# Relay_schematic.net
KiCad netlist of a schematic drawn in Altium Designer
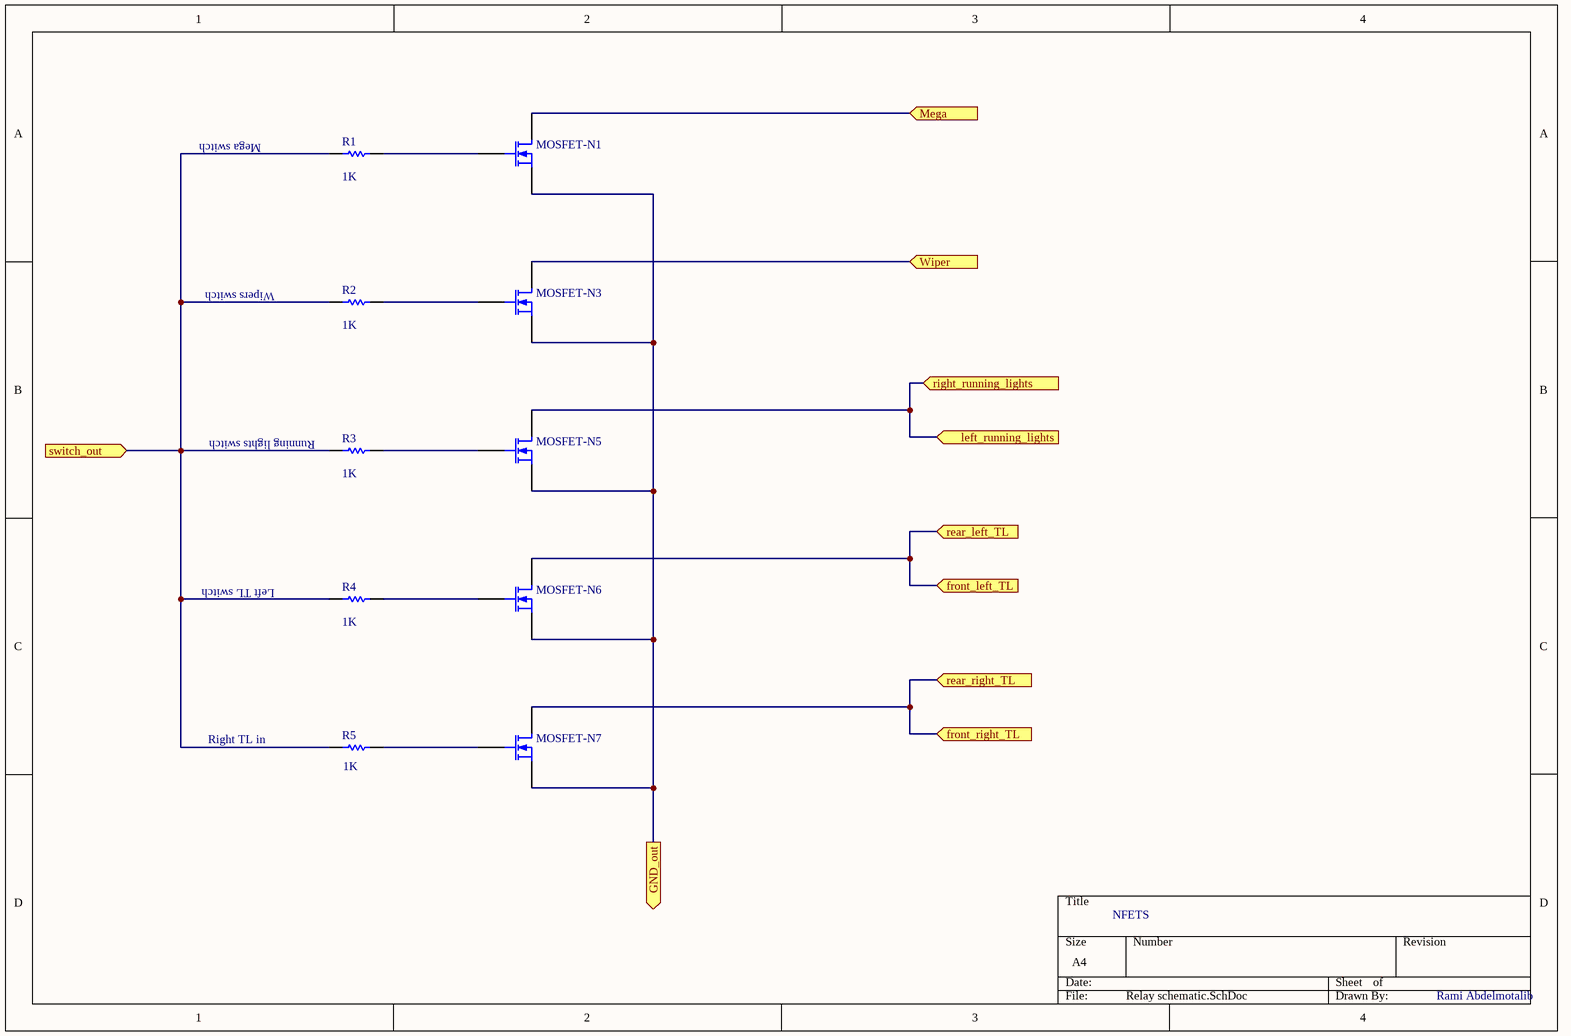
[diagram p0: Relay schematic.SchDoc]

(export (version "E")
  (design (tool "Eeschema 10.0.6"))
  (components
    (comp (ref "MOSFET-N1")
      (value "~")
      (footprint "E3")
      (description "N-Channel MOSFET")
      (fields (field (name "PUBLISHER") "Altium Limited"))
      (libsource (lib "Miscellaneous Devices") (part "MOSFET-N"))
    )
    (comp (ref "MOSFET-N3")
      (value "~")
      (footprint "E3")
      (description "N-Channel MOSFET")
      (fields (field (name "PUBLISHER") "Altium Limited"))
      (libsource (lib "Miscellaneous Devices") (part "MOSFET-N"))
    )
    (comp (ref "MOSFET-N5")
      (value "~")
      (footprint "E3")
      (description "N-Channel MOSFET")
      (fields (field (name "PUBLISHER") "Altium Limited"))
      (libsource (lib "Miscellaneous Devices") (part "MOSFET-N"))
    )
    (comp (ref "MOSFET-N6")
      (value "~")
      (footprint "E3")
      (description "N-Channel MOSFET")
      (fields (field (name "PUBLISHER") "Altium Limited"))
      (libsource (lib "Miscellaneous Devices") (part "MOSFET-N"))
    )
    (comp (ref "MOSFET-N7")
      (value "~")
      (footprint "E3")
      (description "N-Channel MOSFET")
      (fields (field (name "PUBLISHER") "Altium Limited"))
      (libsource (lib "Miscellaneous Devices") (part "MOSFET-N"))
    )
    (comp (ref "R1")
      (value "1K")
      (footprint "AXIAL-0.3")
      (description "Resistor")
      (fields (field (name "PUBLISHER") "Altium Limited"))
      (libsource (lib "Miscellaneous Devices") (part "Res1"))
    )
    (comp (ref "R2")
      (value "1K")
      (footprint "AXIAL-0.3")
      (description "Resistor")
      (fields (field (name "Comment") "Res1") (field (name "PUBLISHER") "Altium Limited"))
      (libsource (lib "Miscellaneous Devices") (part "Res1"))
    )
    (comp (ref "R3")
      (value "1K")
      (footprint "AXIAL-0.3")
      (description "Resistor")
      (fields (field (name "Comment") "Res1") (field (name "PUBLISHER") "Altium Limited"))
      (libsource (lib "Miscellaneous Devices") (part "Res1"))
    )
    (comp (ref "R4")
      (value "1K")
      (footprint "AXIAL-0.3")
      (description "Resistor")
      (fields (field (name "Comment") "Res1") (field (name "PUBLISHER") "Altium Limited"))
      (libsource (lib "Miscellaneous Devices") (part "Res1"))
    )
    (comp (ref "R5")
      (value "1K")
      (footprint "AXIAL-0.3")
      (description "Resistor")
      (fields (field (name "Comment") "Res1") (field (name "PUBLISHER") "Altium Limited"))
      (libsource (lib "Miscellaneous Devices") (part "Res1"))
    )
  )
  (nets
    (net (code "1") (name "/GND_out") (class "Default")
      (node (ref "MOSFET-N1") (pin "3") (pinfunction "S_3") (pintype "passive"))
      (node (ref "MOSFET-N3") (pin "3") (pinfunction "S_3") (pintype "passive"))
      (node (ref "MOSFET-N5") (pin "3") (pinfunction "S_3") (pintype "passive"))
      (node (ref "MOSFET-N6") (pin "3") (pinfunction "S_3") (pintype "passive"))
      (node (ref "MOSFET-N7") (pin "3") (pinfunction "S_3") (pintype "passive"))
    )
    (net (code "2") (name "/Mega") (class "Default")
      (node (ref "MOSFET-N1") (pin "1") (pinfunction "D_1") (pintype "passive"))
    )
    (net (code "3") (name "/Wiper") (class "Default")
      (node (ref "MOSFET-N3") (pin "1") (pinfunction "D_1") (pintype "passive"))
    )
    (net (code "4") (name "/front_left_TL") (class "Default")
      (node (ref "MOSFET-N6") (pin "1") (pinfunction "D_1") (pintype "passive"))
    )
    (net (code "5") (name "/front_right_TL") (class "Default")
      (node (ref "MOSFET-N7") (pin "1") (pinfunction "D_1") (pintype "passive"))
    )
    (net (code "6") (name "/left_running_lights") (class "Default")
      (node (ref "MOSFET-N5") (pin "1") (pinfunction "D_1") (pintype "passive"))
    )
    (net (code "7") (name "/switch_out") (class "Default")
      (node (ref "R1") (pin "1") (pinfunction "1_1") (pintype "passive"))
      (node (ref "R2") (pin "1") (pinfunction "1_1") (pintype "passive"))
      (node (ref "R3") (pin "1") (pinfunction "1_1") (pintype "passive"))
      (node (ref "R4") (pin "1") (pinfunction "1_1") (pintype "passive"))
      (node (ref "R5") (pin "1") (pinfunction "1_1") (pintype "passive"))
    )
    (net (code "8") (name "Net-(MOSFET-N1-G)") (class "Default")
      (node (ref "MOSFET-N1") (pin "2") (pinfunction "G_2") (pintype "passive"))
      (node (ref "R1") (pin "2") (pinfunction "2_2") (pintype "passive"))
    )
    (net (code "9") (name "Net-(MOSFET-N3-G)") (class "Default")
      (node (ref "MOSFET-N3") (pin "2") (pinfunction "G_2") (pintype "passive"))
      (node (ref "R2") (pin "2") (pinfunction "2_2") (pintype "passive"))
    )
    (net (code "10") (name "Net-(MOSFET-N5-G)") (class "Default")
      (node (ref "MOSFET-N5") (pin "2") (pinfunction "G_2") (pintype "passive"))
      (node (ref "R3") (pin "2") (pinfunction "2_2") (pintype "passive"))
    )
    (net (code "11") (name "Net-(MOSFET-N6-G)") (class "Default")
      (node (ref "MOSFET-N6") (pin "2") (pinfunction "G_2") (pintype "passive"))
      (node (ref "R4") (pin "2") (pinfunction "2_2") (pintype "passive"))
    )
    (net (code "12") (name "Net-(MOSFET-N7-G)") (class "Default")
      (node (ref "MOSFET-N7") (pin "2") (pinfunction "G_2") (pintype "passive"))
      (node (ref "R5") (pin "2") (pinfunction "2_2") (pintype "passive"))
    )
  )
)
